# ne555n-astable.net
KiCad netlist of a schematic drawn in EAGLE
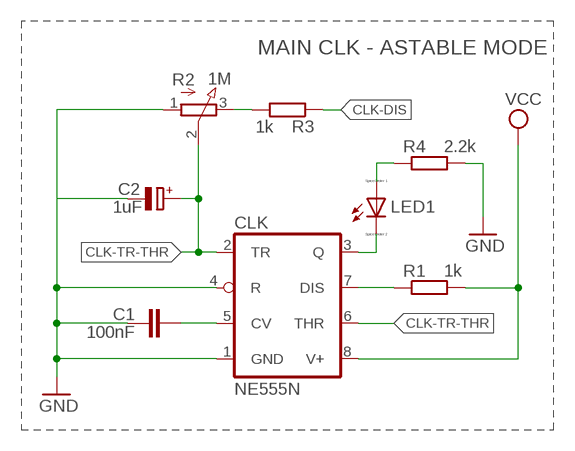
[diagram p0: schematic, sheet 1]

(export (version "E")
  (design (tool "Eeschema 10.0.6"))
  (components
    (comp (ref "C1")
      (value "100nF")
      (footprint "eagle-import:C025-050X050")
      (libsource (lib "eagle-import") (part "C-EU025-050X050"))
    )
    (comp (ref "C2")
      (value "1uF")
      (footprint "eagle-import:E2-5")
      (libsource (lib "eagle-import") (part "CPOL-EUE2-5"))
    )
    (comp (ref "CLK")
      (value "NE555N")
      (footprint "eagle-import:DIL08")
      (libsource (lib "eagle-import") (part "555NNE"))
    )
    (comp (ref "LED1")
      (value "LED_ELD260")
      (footprint "eagle-import:LED_LD260")
      (libsource (lib "eagle-import") (part "LED_ELD260"))
    )
    (comp (ref "R1")
      (value "1k")
      (footprint "eagle-import:0204_5")
      (libsource (lib "eagle-import") (part "R-EU_0204/5"))
    )
    (comp (ref "R2")
      (value "1M")
      (footprint "eagle-import:3RP_1610N")
      (libsource (lib "eagle-import") (part "3RP/1610N"))
    )
    (comp (ref "R3")
      (value "1k")
      (footprint "eagle-import:0204_5")
      (libsource (lib "eagle-import") (part "R-EU_0204/5"))
    )
    (comp (ref "R4")
      (value "2.2k")
      (footprint "eagle-import:0204_5")
      (libsource (lib "eagle-import") (part "R-EU_0204/5"))
    )
  )
  (nets
    (net (code "1") (name "CLK-DIS") (class "Default")
      (node (ref "CLK") (pin "7") (pinfunction "DIS_7") (pintype "input"))
      (node (ref "R1") (pin "1") (pinfunction "1_1") (pintype "passive"))
      (node (ref "R3") (pin "1") (pinfunction "1_1") (pintype "passive"))
    )
    (net (code "2") (name "CLK-TR-THR") (class "Default")
      (node (ref "C2") (pin "+") (pinfunction "+_+") (pintype "passive"))
      (node (ref "CLK") (pin "2") (pinfunction "TR_2") (pintype "input"))
      (node (ref "CLK") (pin "6") (pinfunction "THR_6") (pintype "input"))
      (node (ref "R2") (pin "2") (pinfunction "S_2") (pintype "passive"))
    )
    (net (code "3") (name "GND") (class "Default")
      (node (ref "C1") (pin "1") (pinfunction "1_1") (pintype "passive"))
      (node (ref "C2") (pin "-") (pinfunction "-_-") (pintype "passive"))
      (node (ref "CLK") (pin "1") (pinfunction "GND_1") (pintype "power_in"))
      (node (ref "CLK") (pin "4") (pinfunction "R_4") (pintype "input"))
      (node (ref "R2") (pin "1") (pinfunction "A_1") (pintype "passive"))
      (node (ref "R4") (pin "2") (pinfunction "2_2") (pintype "passive"))
    )
    (net (code "4") (name "Net-(CLK-CV)") (class "Default")
      (node (ref "C1") (pin "2") (pinfunction "2_2") (pintype "passive"))
      (node (ref "CLK") (pin "5") (pinfunction "CV_5") (pintype "input"))
    )
    (net (code "5") (name "Net-(CLK-Q)") (class "Default")
      (node (ref "CLK") (pin "3") (pinfunction "Q_3") (pintype "output"))
      (node (ref "LED1") (pin "K") (pinfunction "C_K") (pintype "passive"))
    )
    (net (code "6") (name "Net-(LED1-PadA)") (class "Default")
      (node (ref "LED1") (pin "A") (pinfunction "A_A") (pintype "passive"))
      (node (ref "R4") (pin "1") (pinfunction "1_1") (pintype "passive"))
    )
    (net (code "7") (name "Net-(R2-E)") (class "Default")
      (node (ref "R2") (pin "3") (pinfunction "E_3") (pintype "passive"))
      (node (ref "R3") (pin "2") (pinfunction "2_2") (pintype "passive"))
    )
    (net (code "8") (name "VCC") (class "Default")
      (node (ref "CLK") (pin "8") (pinfunction "V+_8") (pintype "power_in"))
      (node (ref "R1") (pin "2") (pinfunction "2_2") (pintype "passive"))
    )
  )
)
